# QCopterMV_LED_Sch.net
KiCad netlist of a schematic drawn in Altium Designer
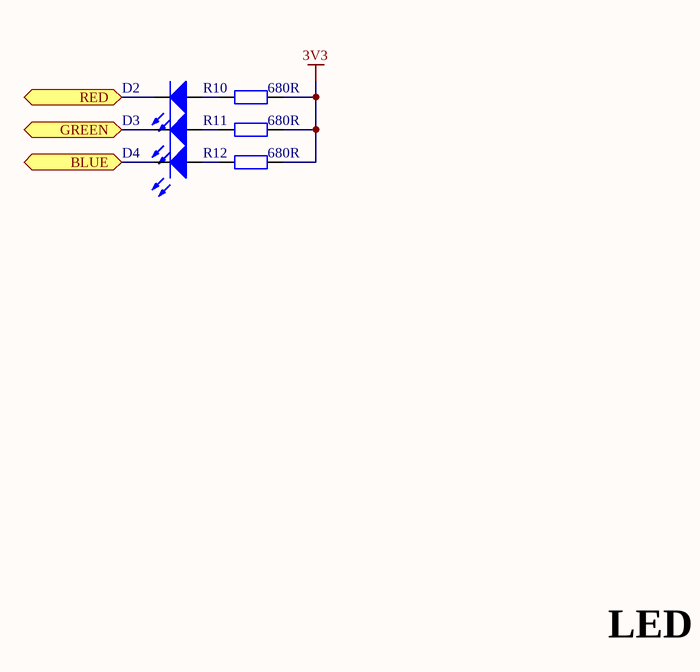
[diagram p0: QCopterMV_LED_Sch.SchDoc]

(export (version "E")
  (design (tool "Eeschema 10.0.6"))
  (components
    (comp (ref "D2")
      (value "LED_0603_RED")
      (footprint "PCB_Active:LED_0603_RED")
      (description "LED")
      (libsource (lib "SCH_Active") (part "LED_0603_RED"))
    )
    (comp (ref "D3")
      (value "LED_0603_GREEN")
      (footprint "PCB_Active:LED_0603_GREEN")
      (description "LED")
      (libsource (lib "SCH_Active") (part "LED_0603_GREEN"))
    )
    (comp (ref "D4")
      (value "LED_0603_BLUE")
      (footprint "PCB_Active:LED_0603_BLUE")
      (description "LED")
      (libsource (lib "SCH_Active") (part "LED_0603_BLUE"))
    )
    (comp (ref "R10")
      (value "680R")
      (footprint "PCB_Passive:RES_0603")
      (description "Resistor")
      (fields (field (name "Comment") "Res_0603"))
      (libsource (lib "SCH_Passive") (part "Res_0603"))
    )
    (comp (ref "R11")
      (value "680R")
      (footprint "PCB_Passive:RES_0603")
      (description "Resistor")
      (fields (field (name "Comment") "Res_0603"))
      (libsource (lib "SCH_Passive") (part "Res_0603"))
    )
    (comp (ref "R12")
      (value "680R")
      (footprint "PCB_Passive:RES_0603")
      (description "Resistor")
      (fields (field (name "Comment") "Res_0603"))
      (libsource (lib "SCH_Passive") (part "Res_0603"))
    )
  )
  (nets
    (net (code "1") (name "/BLUE") (class "Default")
      (node (ref "D4") (pin "2") (pinfunction "K_2") (pintype "passive"))
    )
    (net (code "2") (name "/GREEN") (class "Default")
      (node (ref "D3") (pin "2") (pinfunction "K_2") (pintype "passive"))
    )
    (net (code "3") (name "/RED") (class "Default")
      (node (ref "D2") (pin "2") (pinfunction "K_2") (pintype "passive"))
    )
    (net (code "4") (name "3V3") (class "Default")
      (node (ref "R10") (pin "2") (pinfunction "2_2") (pintype "passive"))
      (node (ref "R11") (pin "2") (pinfunction "2_2") (pintype "passive"))
      (node (ref "R12") (pin "2") (pinfunction "2_2") (pintype "passive"))
    )
    (net (code "5") (name "Net-(D2-A)") (class "Default")
      (node (ref "D2") (pin "1") (pinfunction "A_1") (pintype "passive"))
      (node (ref "R10") (pin "1") (pinfunction "1_1") (pintype "passive"))
    )
    (net (code "6") (name "Net-(D3-A)") (class "Default")
      (node (ref "D3") (pin "1") (pinfunction "A_1") (pintype "passive"))
      (node (ref "R11") (pin "1") (pinfunction "1_1") (pintype "passive"))
    )
    (net (code "7") (name "Net-(D4-A)") (class "Default")
      (node (ref "D4") (pin "1") (pinfunction "A_1") (pintype "passive"))
      (node (ref "R12") (pin "1") (pinfunction "1_1") (pintype "passive"))
    )
  )
)
